# 3_WIZ750SR_ETC.net
KiCad netlist of a schematic drawn in Altium Designer
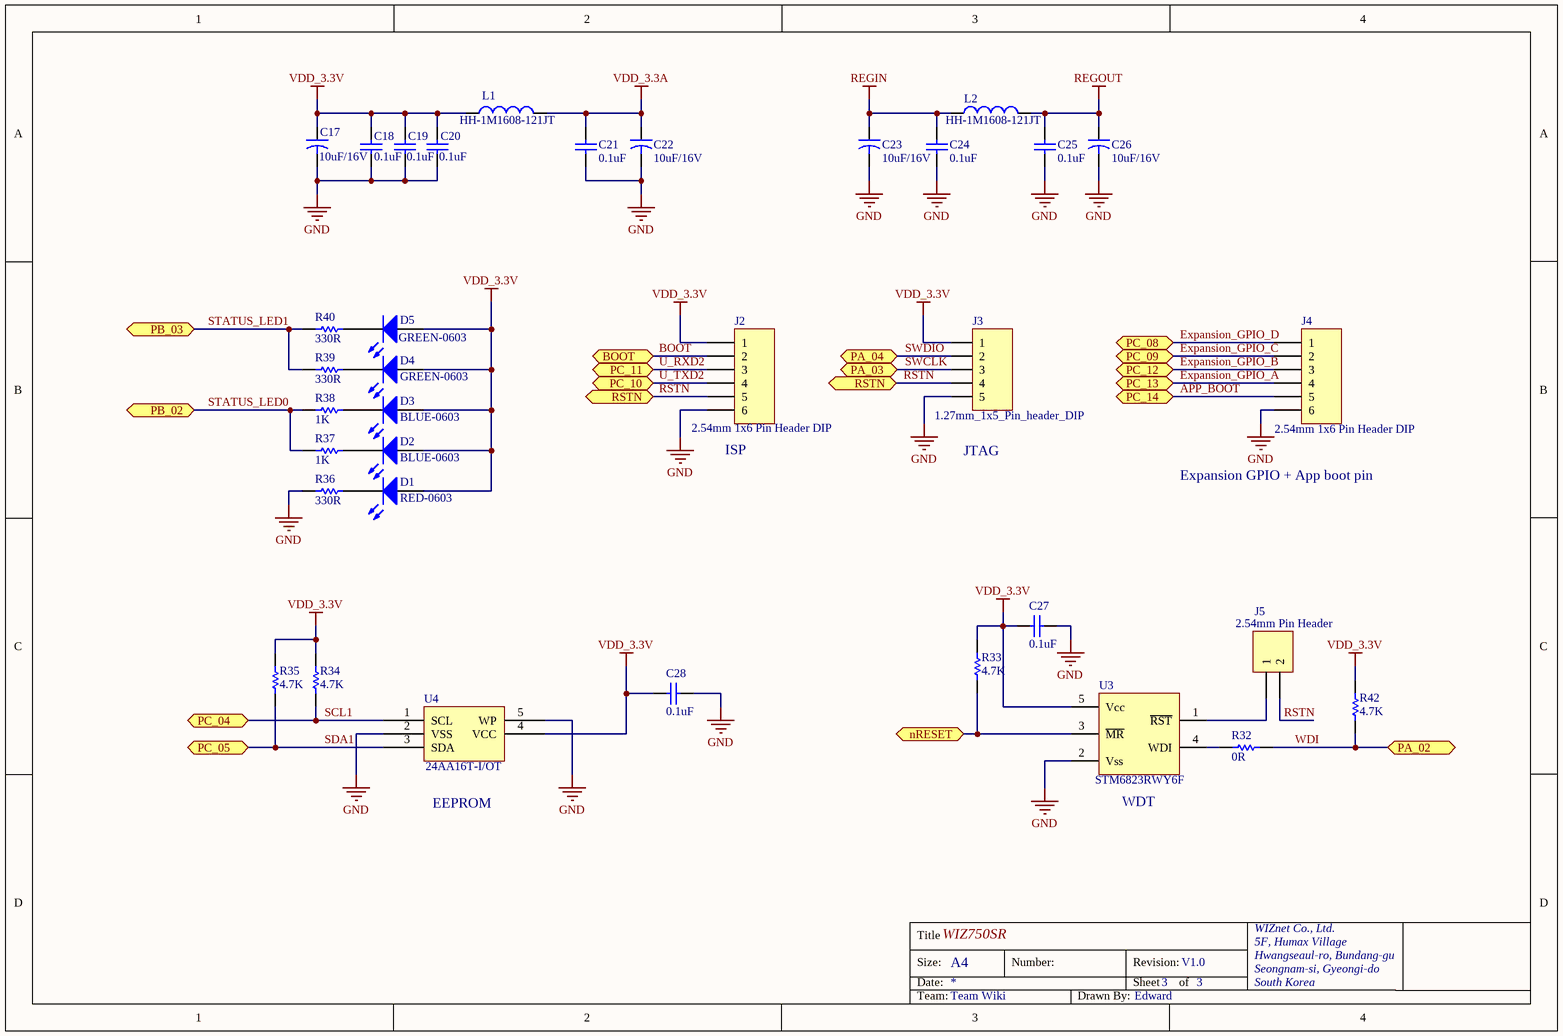
[diagram p0: 3.WIZ750SR_ETC.SchDoc]

(export (version "E")
  (design (tool "Eeschema 10.0.6"))
  (components
    (comp (ref "C17")
      (value "10uF/16V")
      (footprint "CAP-A Size")
      (description "Tantla CAP A Size EIA/IECQ 3216")
      (libsource (lib "Scott_lib") (part "CAP-A Size"))
    )
    (comp (ref "C18")
      (value "0.1uF")
      (footprint "CAP-0402")
      (description "Ceramic CAP 0402(1005)")
      (libsource (lib "Scott_lib") (part "CAP-0402"))
    )
    (comp (ref "C19")
      (value "0.1uF")
      (footprint "CAP-0402")
      (description "Ceramic CAP 0402(1005)")
      (libsource (lib "Scott_lib") (part "CAP-0402"))
    )
    (comp (ref "C20")
      (value "0.1uF")
      (footprint "CAP-0402")
      (description "Ceramic CAP 0402(1005)")
      (libsource (lib "Scott_lib") (part "CAP-0402"))
    )
    (comp (ref "C21")
      (value "0.1uF")
      (footprint "CAP-0402")
      (description "Ceramic CAP 0402(1005)")
      (libsource (lib "Scott_lib") (part "CAP-0402"))
    )
    (comp (ref "C22")
      (value "10uF/16V")
      (footprint "CAP-A Size")
      (description "Tantla CAP A Size EIA/IECQ 3216")
      (libsource (lib "") (part "CAP-A Size_1"))
    )
    (comp (ref "C23")
      (value "10uF/16V")
      (footprint "CAP-A Size")
      (description "Tantla CAP A Size EIA/IECQ 3216")
      (libsource (lib "Scott_lib") (part "CAP-A Size"))
    )
    (comp (ref "C24")
      (value "0.1uF")
      (footprint "CAP-0402")
      (description "Ceramic CAP 0402(1005)")
      (libsource (lib "Scott_lib") (part "CAP-0402"))
    )
    (comp (ref "C25")
      (value "0.1uF")
      (footprint "CAP-0402")
      (description "Ceramic CAP 0402(1005)")
      (libsource (lib "Scott_lib") (part "CAP-0402"))
    )
    (comp (ref "C26")
      (value "10uF/16V")
      (footprint "CAP-A Size")
      (description "Tantla CAP A Size EIA/IECQ 3216")
      (libsource (lib "Scott_lib") (part "CAP-A Size"))
    )
    (comp (ref "C27")
      (value "0.1uF")
      (footprint "CAP-0402")
      (description "Ceramic CAP 0402(1005)")
      (libsource (lib "Scott_lib") (part "CAP-0402"))
    )
    (comp (ref "C28")
      (value "0.1uF")
      (footprint "CAP-0402")
      (description "Ceramic CAP 0402(1005)")
      (libsource (lib "Scott_lib") (part "CAP-0402"))
    )
    (comp (ref "D1")
      (value "RED-0603")
      (footprint "LED-0603-RED")
      (description "LED-0603")
      (libsource (lib "Scott_lib") (part "LED-0603"))
    )
    (comp (ref "D2")
      (value "BLUE-0603")
      (footprint "LED-0603-BLUE")
      (description "LED-0603")
      (libsource (lib "Scott_lib") (part "LED-0603"))
    )
    (comp (ref "D3")
      (value "BLUE-0603")
      (footprint "LED-0603-BLUE")
      (description "LED-0603")
      (libsource (lib "Scott_lib") (part "LED-0603"))
    )
    (comp (ref "D4")
      (value "GREEN-0603")
      (footprint "LED-0603-GREEN")
      (description "LED-0603")
      (libsource (lib "Scott_lib") (part "LED-0603"))
    )
    (comp (ref "D5")
      (value "GREEN-0603")
      (footprint "LED-0603-GREEN")
      (description "LED-0603")
      (libsource (lib "Scott_lib") (part "LED-0603"))
    )
    (comp (ref "J2")
      (value "2.54mm 1x6 Pin Header DIP")
      (footprint "IDC-1X6")
      (description "Header, 6-Pin")
      (fields (field (name "PUBLISHER") "Altium Limited"))
      (libsource (lib "Miscellaneous Connectors") (part "Header 6"))
    )
    (comp (ref "J3")
      (value "1.27mm_1x5_Pin_header_DIP")
      (footprint "IDC-1X5(1.27MM)")
      (libsource (lib "1.27mm_1x5_Pin_header_DIP") (part "1.27mm_1x5_Pin_header_DIP"))
    )
    (comp (ref "J4")
      (value "2.54mm 1x6 Pin Header DIP")
      (footprint "IDC-1X6")
      (description "Header, 6-Pin")
      (fields (field (name "PUBLISHER") "Altium Limited"))
      (libsource (lib "Miscellaneous Connectors") (part "Header 6"))
    )
    (comp (ref "J5")
      (value "2.54mm Pin Header")
      (footprint "IDC-1X2")
      (description "Header, 2-Pin")
      (fields (field (name "PUBLISHER") "Altium Limited"))
      (libsource (lib "Miscellaneous Connectors") (part "Header 2"))
    )
    (comp (ref "L1")
      (value "HH-1M1608-121JT")
      (footprint "IND-0603")
      (description "Inductor 0603(1608)")
      (libsource (lib "Scott_lib") (part "IND-0603"))
    )
    (comp (ref "L2")
      (value "HH-1M1608-121JT")
      (footprint "IND-0603")
      (description "Inductor 0603(1608)")
      (libsource (lib "Scott_lib") (part "IND-0603"))
    )
    (comp (ref "R32")
      (value "0R")
      (footprint "RES-0402")
      (description "RES-0402")
      (libsource (lib "Scott_lib") (part "RES-0402"))
    )
    (comp (ref "R33")
      (value "4.7K")
      (footprint "RES-0402")
      (description "RES-0402")
      (libsource (lib "Scott_lib") (part "RES-0402"))
    )
    (comp (ref "R34")
      (value "4.7K")
      (footprint "RES-0402")
      (description "RES-0402")
      (libsource (lib "Scott_lib") (part "RES-0402"))
    )
    (comp (ref "R35")
      (value "4.7K")
      (footprint "RES-0402")
      (description "RES-0402")
      (libsource (lib "Scott_lib") (part "RES-0402"))
    )
    (comp (ref "R36")
      (value "330R")
      (footprint "RES-0402")
      (description "RES-0402")
      (libsource (lib "Scott_lib") (part "RES-0402"))
    )
    (comp (ref "R37")
      (value "1K")
      (footprint "RES-0402")
      (description "RES-0402")
      (libsource (lib "Scott_lib") (part "RES-0402"))
    )
    (comp (ref "R38")
      (value "1K")
      (footprint "RES-0402")
      (description "RES-0402")
      (libsource (lib "Scott_lib") (part "RES-0402"))
    )
    (comp (ref "R39")
      (value "330R")
      (footprint "RES-0402")
      (description "RES-0402")
      (libsource (lib "Scott_lib") (part "RES-0402"))
    )
    (comp (ref "R40")
      (value "330R")
      (footprint "RES-0402")
      (description "RES-0402")
      (libsource (lib "Scott_lib") (part "RES-0402"))
    )
    (comp (ref "R42")
      (value "4.7K")
      (footprint "RES-0402")
      (description "RES-0402")
      (libsource (lib "Scott_lib") (part "RES-0402"))
    )
    (comp (ref "U3")
      (value "STM6823RWY6F")
      (footprint "SOT-23-5L")
      (description "Manual_Reset SOT23-5")
      (libsource (lib "STM6823") (part "STM6823"))
    )
    (comp (ref "U4")
      (value "24AA16T-I/OT")
      (footprint "SOT-23-5L")
      (description "SOT-23")
      (libsource (lib "24AAxxT-OT") (part "24AAxxT-i-OT"))
    )
  )
  (nets
    (net (code "1") (name "/APP_BOOT") (class "Default")
      (node (ref "J4") (pin "5") (pinfunction "5_5") (pintype "passive"))
    )
    (net (code "2") (name "/BOOT") (class "Default")
      (node (ref "J2") (pin "2") (pinfunction "2_2") (pintype "passive"))
    )
    (net (code "3") (name "/Expansion_GPIO_A") (class "Default")
      (node (ref "J4") (pin "4") (pinfunction "4_4") (pintype "passive"))
    )
    (net (code "4") (name "/Expansion_GPIO_B") (class "Default")
      (node (ref "J4") (pin "3") (pinfunction "3_3") (pintype "passive"))
    )
    (net (code "5") (name "/Expansion_GPIO_C") (class "Default")
      (node (ref "J4") (pin "2") (pinfunction "2_2") (pintype "passive"))
    )
    (net (code "6") (name "/Expansion_GPIO_D") (class "Default")
      (node (ref "J4") (pin "1") (pinfunction "1_1") (pintype "passive"))
    )
    (net (code "7") (name "/RSTN") (class "Default")
      (node (ref "J2") (pin "5") (pinfunction "5_5") (pintype "passive"))
      (node (ref "J3") (pin "4") (pinfunction "4_4") (pintype "passive"))
      (node (ref "J5") (pin "2") (pinfunction "2_2") (pintype "passive"))
    )
    (net (code "8") (name "/SCL1") (class "Default")
      (node (ref "R34") (pin "1") (pinfunction "1_1") (pintype "passive"))
      (node (ref "U4") (pin "1") (pinfunction "SCL_1") (pintype "passive"))
    )
    (net (code "9") (name "/SDA1") (class "Default")
      (node (ref "R35") (pin "1") (pinfunction "1_1") (pintype "passive"))
      (node (ref "U4") (pin "3") (pinfunction "SDA_3") (pintype "passive"))
    )
    (net (code "10") (name "/STATUS_LED0") (class "Default")
      (node (ref "R37") (pin "2") (pinfunction "2_2") (pintype "passive"))
      (node (ref "R38") (pin "2") (pinfunction "2_2") (pintype "passive"))
    )
    (net (code "11") (name "/STATUS_LED1") (class "Default")
      (node (ref "R39") (pin "2") (pinfunction "2_2") (pintype "passive"))
      (node (ref "R40") (pin "2") (pinfunction "2_2") (pintype "passive"))
    )
    (net (code "12") (name "/SWCLK") (class "Default")
      (node (ref "J3") (pin "3") (pinfunction "3_3") (pintype "passive"))
    )
    (net (code "13") (name "/SWDIO") (class "Default")
      (node (ref "J3") (pin "2") (pinfunction "2_2") (pintype "passive"))
    )
    (net (code "14") (name "/U_RXD2") (class "Default")
      (node (ref "J2") (pin "3") (pinfunction "3_3") (pintype "passive"))
    )
    (net (code "15") (name "/U_TXD2") (class "Default")
      (node (ref "J2") (pin "4") (pinfunction "4_4") (pintype "passive"))
    )
    (net (code "16") (name "/WDI") (class "Default")
      (node (ref "R32") (pin "1") (pinfunction "1_1") (pintype "passive"))
      (node (ref "R42") (pin "2") (pinfunction "2_2") (pintype "passive"))
    )
    (net (code "17") (name "/nRESET") (class "Default")
      (node (ref "R33") (pin "1") (pinfunction "1_1") (pintype "passive"))
      (node (ref "U3") (pin "3") (pinfunction "MR_3") (pintype "passive"))
    )
    (net (code "18") (name "GND") (class "Default")
      (node (ref "C17") (pin "2") (pinfunction "2_2") (pintype "passive"))
      (node (ref "C18") (pin "1") (pinfunction "1_1") (pintype "passive"))
      (node (ref "C19") (pin "1") (pinfunction "1_1") (pintype "passive"))
      (node (ref "C20") (pin "1") (pinfunction "1_1") (pintype "passive"))
      (node (ref "C21") (pin "1") (pinfunction "1_1") (pintype "passive"))
      (node (ref "C22") (pin "2") (pinfunction "2_2") (pintype "passive"))
      (node (ref "C23") (pin "2") (pinfunction "2_2") (pintype "passive"))
      (node (ref "C24") (pin "1") (pinfunction "1_1") (pintype "passive"))
      (node (ref "C25") (pin "1") (pinfunction "1_1") (pintype "passive"))
      (node (ref "C26") (pin "2") (pinfunction "2_2") (pintype "passive"))
      (node (ref "C27") (pin "1") (pinfunction "1_1") (pintype "passive"))
      (node (ref "C28") (pin "1") (pinfunction "1_1") (pintype "passive"))
      (node (ref "J2") (pin "6") (pinfunction "6_6") (pintype "passive"))
      (node (ref "J3") (pin "5") (pinfunction "5_5") (pintype "passive"))
      (node (ref "J4") (pin "6") (pinfunction "6_6") (pintype "passive"))
      (node (ref "R36") (pin "2") (pinfunction "2_2") (pintype "passive"))
      (node (ref "U3") (pin "2") (pinfunction "Vss_2") (pintype "passive"))
      (node (ref "U4") (pin "2") (pinfunction "VSS_2") (pintype "passive"))
      (node (ref "U4") (pin "5") (pinfunction "WP_5") (pintype "passive"))
    )
    (net (code "19") (name "Net-(D1-K)") (class "Default")
      (node (ref "D1") (pin "2") (pinfunction "K_2") (pintype "passive"))
      (node (ref "R36") (pin "1") (pinfunction "1_1") (pintype "passive"))
    )
    (net (code "20") (name "Net-(D2-K)") (class "Default")
      (node (ref "D2") (pin "2") (pinfunction "K_2") (pintype "passive"))
      (node (ref "R37") (pin "1") (pinfunction "1_1") (pintype "passive"))
    )
    (net (code "21") (name "Net-(D3-K)") (class "Default")
      (node (ref "D3") (pin "2") (pinfunction "K_2") (pintype "passive"))
      (node (ref "R38") (pin "1") (pinfunction "1_1") (pintype "passive"))
    )
    (net (code "22") (name "Net-(D4-K)") (class "Default")
      (node (ref "D4") (pin "2") (pinfunction "K_2") (pintype "passive"))
      (node (ref "R39") (pin "1") (pinfunction "1_1") (pintype "passive"))
    )
    (net (code "23") (name "Net-(D5-K)") (class "Default")
      (node (ref "D5") (pin "2") (pinfunction "K_2") (pintype "passive"))
      (node (ref "R40") (pin "1") (pinfunction "1_1") (pintype "passive"))
    )
    (net (code "24") (name "Net-(U3-RST)") (class "Default")
      (node (ref "J5") (pin "1") (pinfunction "1_1") (pintype "passive"))
      (node (ref "U3") (pin "1") (pinfunction "RST_1") (pintype "passive"))
    )
    (net (code "25") (name "Net-(U3-WDI)") (class "Default")
      (node (ref "R32") (pin "2") (pinfunction "2_2") (pintype "passive"))
      (node (ref "U3") (pin "4") (pinfunction "WDI_4") (pintype "passive"))
    )
    (net (code "26") (name "REGIN") (class "Default")
      (node (ref "C23") (pin "1") (pinfunction "1_1") (pintype "passive"))
      (node (ref "C24") (pin "2") (pinfunction "2_2") (pintype "passive"))
      (node (ref "L2") (pin "1") (pinfunction "1_1") (pintype "passive"))
    )
    (net (code "27") (name "REGOUT") (class "Default")
      (node (ref "C25") (pin "2") (pinfunction "2_2") (pintype "passive"))
      (node (ref "C26") (pin "1") (pinfunction "1_1") (pintype "passive"))
      (node (ref "L2") (pin "2") (pinfunction "2_2") (pintype "passive"))
    )
    (net (code "28") (name "VDD_3.3A") (class "Default")
      (node (ref "C21") (pin "2") (pinfunction "2_2") (pintype "passive"))
      (node (ref "C22") (pin "1") (pinfunction "1_1") (pintype "passive"))
      (node (ref "L1") (pin "2") (pinfunction "2_2") (pintype "passive"))
    )
    (net (code "29") (name "VDD_3.3V") (class "Default")
      (node (ref "C17") (pin "1") (pinfunction "1_1") (pintype "passive"))
      (node (ref "C18") (pin "2") (pinfunction "2_2") (pintype "passive"))
      (node (ref "C19") (pin "2") (pinfunction "2_2") (pintype "passive"))
      (node (ref "C20") (pin "2") (pinfunction "2_2") (pintype "passive"))
      (node (ref "C27") (pin "2") (pinfunction "2_2") (pintype "passive"))
      (node (ref "C28") (pin "2") (pinfunction "2_2") (pintype "passive"))
      (node (ref "D1") (pin "1") (pinfunction "A_1") (pintype "passive"))
      (node (ref "D2") (pin "1") (pinfunction "A_1") (pintype "passive"))
      (node (ref "D3") (pin "1") (pinfunction "A_1") (pintype "passive"))
      (node (ref "D4") (pin "1") (pinfunction "A_1") (pintype "passive"))
      (node (ref "D5") (pin "1") (pinfunction "A_1") (pintype "passive"))
      (node (ref "J2") (pin "1") (pinfunction "1_1") (pintype "passive"))
      (node (ref "J3") (pin "1") (pinfunction "1_1") (pintype "passive"))
      (node (ref "L1") (pin "1") (pinfunction "1_1") (pintype "passive"))
      (node (ref "R33") (pin "2") (pinfunction "2_2") (pintype "passive"))
      (node (ref "R34") (pin "2") (pinfunction "2_2") (pintype "passive"))
      (node (ref "R35") (pin "2") (pinfunction "2_2") (pintype "passive"))
      (node (ref "R42") (pin "1") (pinfunction "1_1") (pintype "passive"))
      (node (ref "U3") (pin "5") (pinfunction "Vcc_5") (pintype "passive"))
      (node (ref "U4") (pin "4") (pinfunction "VCC_4") (pintype "passive"))
    )
  )
)
